# ramanPi_controlBoard.net
KiCad netlist of a schematic drawn in EAGLE
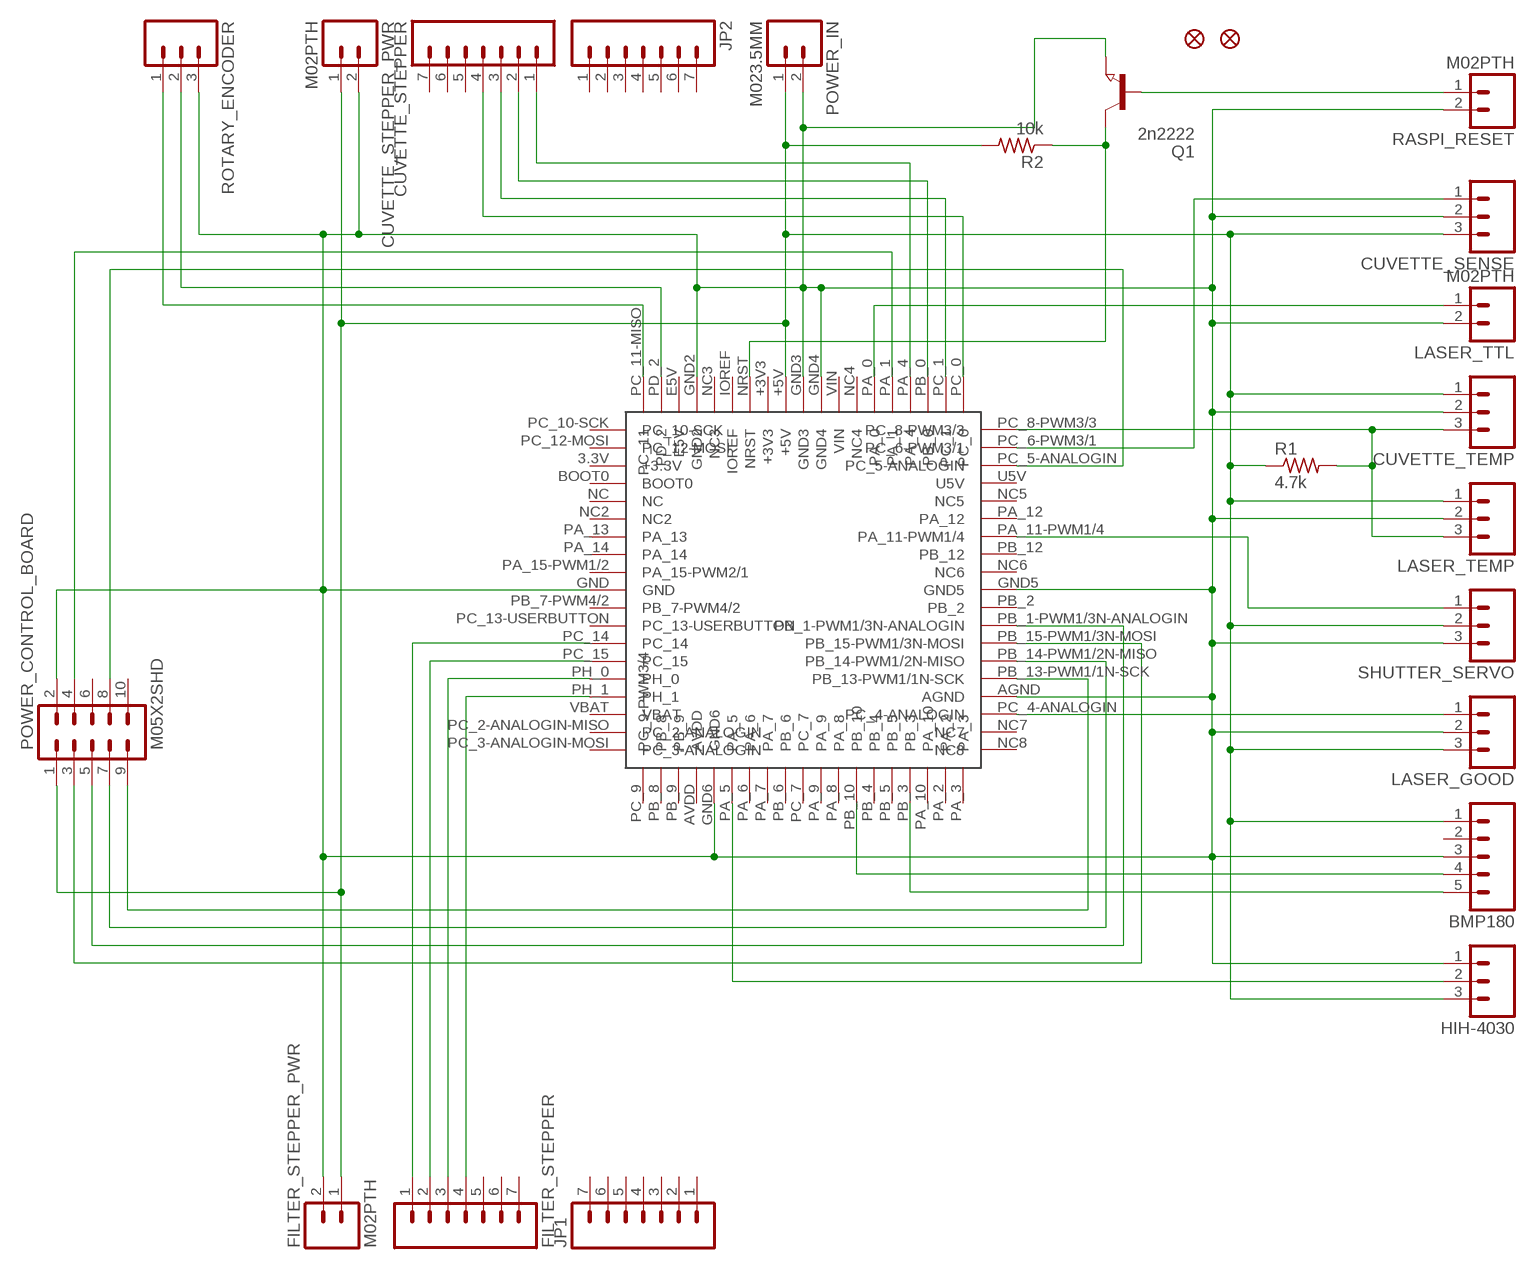
[diagram p0: schematic, sheet 1]

(export (version "E")
  (design (tool "Eeschema 10.0.6"))
  (components
    (comp (ref "BMP180")
      (value "M05PTH")
      (footprint "eagle-import:1X05")
      (libsource (lib "eagle-import") (part "M05PTH"))
    )
    (comp (ref "CUVETTE_SENSE")
      (value "M03PTH")
      (footprint "eagle-import:1X03")
      (libsource (lib "eagle-import") (part "M03PTH"))
    )
    (comp (ref "CUVETTE_STEPPER")
      (value "M07")
      (footprint "eagle-import:1X07")
      (libsource (lib "eagle-import") (part "M07"))
    )
    (comp (ref "CUVETTE_STEPPER_PWR")
      (value "M02PTH")
      (footprint "eagle-import:1X02")
      (libsource (lib "eagle-import") (part "M02PTH"))
    )
    (comp (ref "CUVETTE_TEMP")
      (value "M03PTH")
      (footprint "eagle-import:1X03")
      (libsource (lib "eagle-import") (part "M03PTH"))
    )
    (comp (ref "FID1")
      (value "FIDUCIAL1X2")
      (footprint "eagle-import:FIDUCIAL-1X2")
      (libsource (lib "eagle-import") (part "FIDUCIAL1X2"))
    )
    (comp (ref "FID2")
      (value "FIDUCIAL1X2")
      (footprint "eagle-import:FIDUCIAL-1X2")
      (libsource (lib "eagle-import") (part "FIDUCIAL1X2"))
    )
    (comp (ref "FILTER_STEPPER")
      (value "M07")
      (footprint "eagle-import:1X07")
      (libsource (lib "eagle-import") (part "M07"))
    )
    (comp (ref "FILTER_STEPPER_PWR")
      (value "M02PTH")
      (footprint "eagle-import:1X02")
      (libsource (lib "eagle-import") (part "M02PTH"))
    )
    (comp (ref "HIH-4030")
      (value "M03PTH")
      (footprint "eagle-import:1X03")
      (libsource (lib "eagle-import") (part "M03PTH"))
    )
    (comp (ref "JP1")
      (value "M07")
      (footprint "eagle-import:1X07")
      (libsource (lib "eagle-import") (part "M07"))
    )
    (comp (ref "JP2")
      (value "M07")
      (footprint "eagle-import:1X07")
      (libsource (lib "eagle-import") (part "M07"))
    )
    (comp (ref "LASER_GOOD")
      (value "M03PTH")
      (footprint "eagle-import:1X03")
      (libsource (lib "eagle-import") (part "M03PTH"))
    )
    (comp (ref "LASER_TEMP")
      (value "M03PTH")
      (footprint "eagle-import:1X03")
      (libsource (lib "eagle-import") (part "M03PTH"))
    )
    (comp (ref "LASER_TTL")
      (value "M02PTH")
      (footprint "eagle-import:1X02")
      (libsource (lib "eagle-import") (part "M02PTH"))
    )
    (comp (ref "POWER_CONTROL_BOARD")
      (value "M05X2SHD")
      (footprint "eagle-import:2X5-SHROUDED")
      (libsource (lib "eagle-import") (part "M05X2SHD"))
    )
    (comp (ref "POWER_IN")
      (value "M023.5MM")
      (footprint "eagle-import:SCREWTERMINAL-3.5MM-2")
      (libsource (lib "eagle-import") (part "M023.5MM"))
    )
    (comp (ref "Q1")
      (value "2n2222")
      (footprint "eagle-import:SOT23")
      (libsource (lib "eagle-import") (part "NPN-TRANSISTOR_SOT23"))
    )
    (comp (ref "R1")
      (value "4.7k")
      (footprint "eagle-import:M1206")
      (libsource (lib "eagle-import") (part "R-US_M1206"))
    )
    (comp (ref "R2")
      (value "10k")
      (footprint "eagle-import:M1206")
      (libsource (lib "eagle-import") (part "R-US_M1206"))
    )
    (comp (ref "RASPI_RESET")
      (value "M02PTH")
      (footprint "eagle-import:1X02")
      (libsource (lib "eagle-import") (part "M02PTH"))
    )
    (comp (ref "ROTARY_ENCODER")
      (value "M03PTH")
      (footprint "eagle-import:1X03")
      (libsource (lib "eagle-import") (part "M03PTH"))
    )
    (comp (ref "SHUTTER_SERVO")
      (value "M03PTH")
      (footprint "eagle-import:1X03")
      (libsource (lib "eagle-import") (part "M03PTH"))
    )
    (comp (ref "U$1")
      (value "STNUCLEOF401RE")
      (footprint "eagle-import:F401-RE")
      (libsource (lib "eagle-import") (part "STNUCLEOF401RE"))
    )
  )
  (nets
    (net (code "1") (name "/+3.3V") (class "Default")
      (node (ref "U$1") (pin "3.3V") (pinfunction "+3.3V_3.3V") (pintype "power_in"))
    )
    (net (code "2") (name "/+3V3") (class "Default")
      (node (ref "U$1") (pin "+3V3") (pinfunction "+3V3_+3V3") (pintype "power_in"))
    )
    (net (code "3") (name "/AVDD") (class "Default")
      (node (ref "U$1") (pin "AVDD") (pinfunction "AVDD_AVDD") (pintype "power_in"))
    )
    (net (code "4") (name "/E5V") (class "Default")
      (node (ref "U$1") (pin "E5V") (pinfunction "E5V_E5V") (pintype "power_in"))
    )
    (net (code "5") (name "/U5V") (class "Default")
      (node (ref "U$1") (pin "U5V") (pinfunction "U5V_U5V") (pintype "power_in"))
    )
    (net (code "6") (name "/VBAT") (class "Default")
      (node (ref "U$1") (pin "VBAT") (pinfunction "VBAT_VBAT") (pintype "power_in"))
    )
    (net (code "7") (name "/VIN") (class "Default")
      (node (ref "U$1") (pin "VIN") (pinfunction "VIN_VIN") (pintype "power_in"))
    )
    (net (code "8") (name "Net-(BMP180-Pad1)") (class "Default")
      (node (ref "BMP180") (pin "1") (pinfunction "1_1") (pintype "passive"))
      (node (ref "CUVETTE_SENSE") (pin "3") (pinfunction "3_3") (pintype "passive"))
      (node (ref "CUVETTE_STEPPER_PWR") (pin "1") (pinfunction "1_1") (pintype "passive"))
      (node (ref "CUVETTE_TEMP") (pin "1") (pinfunction "1_1") (pintype "passive"))
      (node (ref "FILTER_STEPPER_PWR") (pin "1") (pinfunction "1_1") (pintype "passive"))
      (node (ref "HIH-4030") (pin "3") (pinfunction "3_3") (pintype "passive"))
      (node (ref "LASER_GOOD") (pin "3") (pinfunction "3_3") (pintype "passive"))
      (node (ref "LASER_TEMP") (pin "1") (pinfunction "1_1") (pintype "passive"))
      (node (ref "POWER_CONTROL_BOARD") (pin "1") (pinfunction "1_1") (pintype "passive"))
      (node (ref "POWER_IN") (pin "1") (pinfunction "1_1") (pintype "passive"))
      (node (ref "R1") (pin "1") (pinfunction "1_1") (pintype "passive"))
      (node (ref "R2") (pin "2") (pinfunction "2_2") (pintype "passive"))
      (node (ref "SHUTTER_SERVO") (pin "2") (pinfunction "2_2") (pintype "passive"))
      (node (ref "U$1") (pin "+5V") (pinfunction "+5V_+5V") (pintype "power_in"))
    )
    (net (code "9") (name "Net-(BMP180-Pad4)") (class "Default")
      (node (ref "BMP180") (pin "4") (pinfunction "4_4") (pintype "passive"))
      (node (ref "U$1") (pin "PB_10") (pinfunction "PB_10_PB_10") (pintype "bidirectional"))
    )
    (net (code "10") (name "Net-(BMP180-Pad5)") (class "Default")
      (node (ref "BMP180") (pin "5") (pinfunction "5_5") (pintype "passive"))
      (node (ref "U$1") (pin "PB_3") (pinfunction "PB_3_PB_3") (pintype "bidirectional"))
    )
    (net (code "11") (name "Net-(CUVETTE_SENSE-Pad1)") (class "Default")
      (node (ref "CUVETTE_SENSE") (pin "1") (pinfunction "1_1") (pintype "passive"))
      (node (ref "U$1") (pin "PC_6-PWM3/1") (pinfunction "PC_6-PWM3/1_PC_6-PWM3/1") (pintype "bidirectional"))
    )
    (net (code "12") (name "Net-(CUVETTE_STEPPER-Pad1)") (class "Default")
      (node (ref "CUVETTE_STEPPER") (pin "1") (pinfunction "1_1") (pintype "passive"))
      (node (ref "U$1") (pin "PA_4") (pinfunction "PA_4_PA_4") (pintype "bidirectional"))
    )
    (net (code "13") (name "Net-(CUVETTE_STEPPER-Pad2)") (class "Default")
      (node (ref "CUVETTE_STEPPER") (pin "2") (pinfunction "2_2") (pintype "passive"))
      (node (ref "U$1") (pin "PB_0") (pinfunction "PB_0_PB_0") (pintype "bidirectional"))
    )
    (net (code "14") (name "Net-(CUVETTE_STEPPER-Pad3)") (class "Default")
      (node (ref "CUVETTE_STEPPER") (pin "3") (pinfunction "3_3") (pintype "passive"))
      (node (ref "U$1") (pin "PC_1") (pinfunction "PC_1_PC_1") (pintype "bidirectional"))
    )
    (net (code "15") (name "Net-(CUVETTE_STEPPER-Pad4)") (class "Default")
      (node (ref "CUVETTE_STEPPER") (pin "4") (pinfunction "4_4") (pintype "passive"))
      (node (ref "U$1") (pin "PC_0") (pinfunction "PC_0_PC_0") (pintype "bidirectional"))
    )
    (net (code "16") (name "Net-(CUVETTE_TEMP-Pad3)") (class "Default")
      (node (ref "CUVETTE_TEMP") (pin "3") (pinfunction "3_3") (pintype "passive"))
      (node (ref "LASER_TEMP") (pin "3") (pinfunction "3_3") (pintype "passive"))
      (node (ref "R1") (pin "2") (pinfunction "2_2") (pintype "passive"))
      (node (ref "U$1") (pin "PC_8-PWM3/3") (pinfunction "PC_8-PWM3/3_PC_8-PWM3/3") (pintype "bidirectional"))
    )
    (net (code "17") (name "Net-(FILTER_STEPPER-Pad1)") (class "Default")
      (node (ref "FILTER_STEPPER") (pin "1") (pinfunction "1_1") (pintype "passive"))
      (node (ref "U$1") (pin "PC_14") (pinfunction "PC_14_PC_14") (pintype "bidirectional"))
    )
    (net (code "18") (name "Net-(FILTER_STEPPER-Pad2)") (class "Default")
      (node (ref "FILTER_STEPPER") (pin "2") (pinfunction "2_2") (pintype "passive"))
      (node (ref "U$1") (pin "PC_15") (pinfunction "PC_15_PC_15") (pintype "bidirectional"))
    )
    (net (code "19") (name "Net-(FILTER_STEPPER-Pad3)") (class "Default")
      (node (ref "FILTER_STEPPER") (pin "3") (pinfunction "3_3") (pintype "passive"))
      (node (ref "U$1") (pin "PH_0") (pinfunction "PH_0_PH_0") (pintype "bidirectional"))
    )
    (net (code "20") (name "Net-(FILTER_STEPPER-Pad4)") (class "Default")
      (node (ref "FILTER_STEPPER") (pin "4") (pinfunction "4_4") (pintype "passive"))
      (node (ref "U$1") (pin "PH_1") (pinfunction "PH_1_PH_1") (pintype "bidirectional"))
    )
    (net (code "21") (name "Net-(HIH-4030-Pad2)") (class "Default")
      (node (ref "HIH-4030") (pin "2") (pinfunction "2_2") (pintype "passive"))
      (node (ref "U$1") (pin "PA_5") (pinfunction "PA_5_PA_5") (pintype "bidirectional"))
    )
    (net (code "22") (name "Net-(LASER_GOOD-Pad1)") (class "Default")
      (node (ref "LASER_GOOD") (pin "1") (pinfunction "1_1") (pintype "passive"))
      (node (ref "U$1") (pin "PC_4-ANALOGIN") (pinfunction "PC_4-ANALOGIN_PC_4-ANALOGIN") (pintype "bidirectional"))
    )
    (net (code "23") (name "Net-(LASER_TTL-Pad1)") (class "Default")
      (node (ref "LASER_TTL") (pin "1") (pinfunction "1_1") (pintype "passive"))
      (node (ref "U$1") (pin "PA_0") (pinfunction "PA_0_PA_0") (pintype "bidirectional"))
    )
    (net (code "24") (name "Net-(POWER_CONTROL_BOARD-Pad3)") (class "Default")
      (node (ref "POWER_CONTROL_BOARD") (pin "3") (pinfunction "3_3") (pintype "passive"))
      (node (ref "U$1") (pin "PB_15-PWM1/3N-MOSI") (pinfunction "PB_15-PWM1/3N-MOSI_PB_15-PWM1/3N-MOSI") (pintype "bidirectional"))
    )
    (net (code "25") (name "Net-(POWER_CONTROL_BOARD-Pad4)") (class "Default")
      (node (ref "POWER_CONTROL_BOARD") (pin "4") (pinfunction "4_4") (pintype "passive"))
      (node (ref "U$1") (pin "PA_1") (pinfunction "PA_1_PA_1") (pintype "bidirectional"))
    )
    (net (code "26") (name "Net-(POWER_CONTROL_BOARD-Pad5)") (class "Default")
      (node (ref "POWER_CONTROL_BOARD") (pin "5") (pinfunction "5_5") (pintype "passive"))
      (node (ref "U$1") (pin "PB_1-PWM1/3N-ANALOGIN") (pinfunction "PB_1-PWM1/3N-ANALOGIN_PB_1-PWM1/3N-ANALOGIN") (pintype "bidirectional"))
    )
    (net (code "27") (name "Net-(POWER_CONTROL_BOARD-Pad7)") (class "Default")
      (node (ref "POWER_CONTROL_BOARD") (pin "7") (pinfunction "7_7") (pintype "passive"))
      (node (ref "U$1") (pin "PB_14-PWM1/2N-MISO") (pinfunction "PB_14-PWM1/2N-MISO_PB_14-PWM1/2N-MISO") (pintype "bidirectional"))
    )
    (net (code "28") (name "Net-(POWER_CONTROL_BOARD-Pad8)") (class "Default")
      (node (ref "POWER_CONTROL_BOARD") (pin "8") (pinfunction "8_8") (pintype "passive"))
      (node (ref "U$1") (pin "PC_5-ANALOGIN") (pinfunction "PC_5-ANALOGIN_PC_5-ANALOGIN") (pintype "bidirectional"))
    )
    (net (code "29") (name "Net-(POWER_CONTROL_BOARD-Pad9)") (class "Default")
      (node (ref "POWER_CONTROL_BOARD") (pin "9") (pinfunction "9_9") (pintype "passive"))
      (node (ref "U$1") (pin "PB_13-PWM1/1N-SCK") (pinfunction "PB_13-PWM1/1N-SCK_PB_13-PWM1/1N-SCK") (pintype "bidirectional"))
    )
    (net (code "30") (name "Net-(Q1-B)") (class "Default")
      (node (ref "Q1") (pin "1") (pinfunction "B_1") (pintype "passive"))
      (node (ref "RASPI_RESET") (pin "1") (pinfunction "1_1") (pintype "passive"))
    )
    (net (code "31") (name "Net-(Q1-C)") (class "Default")
      (node (ref "Q1") (pin "3") (pinfunction "C_3") (pintype "passive"))
      (node (ref "R2") (pin "1") (pinfunction "1_1") (pintype "passive"))
      (node (ref "U$1") (pin "NRST") (pinfunction "NRST_NRST") (pintype "bidirectional"))
    )
    (net (code "32") (name "Net-(Q1-E)") (class "Default")
      (node (ref "BMP180") (pin "3") (pinfunction "3_3") (pintype "passive"))
      (node (ref "CUVETTE_SENSE") (pin "2") (pinfunction "2_2") (pintype "passive"))
      (node (ref "CUVETTE_STEPPER_PWR") (pin "2") (pinfunction "2_2") (pintype "passive"))
      (node (ref "CUVETTE_TEMP") (pin "2") (pinfunction "2_2") (pintype "passive"))
      (node (ref "FILTER_STEPPER_PWR") (pin "2") (pinfunction "2_2") (pintype "passive"))
      (node (ref "HIH-4030") (pin "1") (pinfunction "1_1") (pintype "passive"))
      (node (ref "LASER_GOOD") (pin "2") (pinfunction "2_2") (pintype "passive"))
      (node (ref "LASER_TEMP") (pin "2") (pinfunction "2_2") (pintype "passive"))
      (node (ref "LASER_TTL") (pin "2") (pinfunction "2_2") (pintype "passive"))
      (node (ref "POWER_CONTROL_BOARD") (pin "2") (pinfunction "2_2") (pintype "passive"))
      (node (ref "POWER_IN") (pin "2") (pinfunction "2_2") (pintype "passive"))
      (node (ref "Q1") (pin "2") (pinfunction "E_2") (pintype "passive"))
      (node (ref "RASPI_RESET") (pin "2") (pinfunction "2_2") (pintype "passive"))
      (node (ref "ROTARY_ENCODER") (pin "3") (pinfunction "3_3") (pintype "passive"))
      (node (ref "SHUTTER_SERVO") (pin "3") (pinfunction "3_3") (pintype "passive"))
      (node (ref "U$1") (pin "AGND") (pinfunction "AGND_AGND") (pintype "power_in"))
      (node (ref "U$1") (pin "GND") (pinfunction "GND_GND") (pintype "power_in"))
      (node (ref "U$1") (pin "GND2") (pinfunction "GND2_GND2") (pintype "power_in"))
      (node (ref "U$1") (pin "GND3") (pinfunction "GND3_GND3") (pintype "power_in"))
      (node (ref "U$1") (pin "GND4") (pinfunction "GND4_GND4") (pintype "power_in"))
      (node (ref "U$1") (pin "GND5") (pinfunction "GND5_GND5") (pintype "power_in"))
      (node (ref "U$1") (pin "GND6") (pinfunction "GND6_GND6") (pintype "power_in"))
    )
    (net (code "33") (name "Net-(ROTARY_ENCODER-Pad2)") (class "Default")
      (node (ref "ROTARY_ENCODER") (pin "2") (pinfunction "2_2") (pintype "passive"))
      (node (ref "U$1") (pin "PD_2") (pinfunction "PD_2_PD_2") (pintype "bidirectional"))
    )
    (net (code "34") (name "Net-(SHUTTER_SERVO-Pad1)") (class "Default")
      (node (ref "SHUTTER_SERVO") (pin "1") (pinfunction "1_1") (pintype "passive"))
      (node (ref "U$1") (pin "PA_11-PWM1/4") (pinfunction "PA_11-PWM1/4_PA_11-PWM1/4") (pintype "bidirectional"))
    )
    (net (code "35") (name "Net-(U$1-PC_11)") (class "Default")
      (node (ref "ROTARY_ENCODER") (pin "1") (pinfunction "1_1") (pintype "passive"))
      (node (ref "U$1") (pin "PC_11-MISO") (pinfunction "PC_11_PC_11-MISO") (pintype "bidirectional"))
    )
    (net (code "36") (name "unconnected-(BMP180-Pad2)") (class "Default")
      (node (ref "BMP180") (pin "2") (pinfunction "2_2") (pintype "passive"))
    )
    (net (code "37") (name "unconnected-(CUVETTE_STEPPER-Pad5)") (class "Default")
      (node (ref "CUVETTE_STEPPER") (pin "5") (pinfunction "5_5") (pintype "passive"))
    )
    (net (code "38") (name "unconnected-(CUVETTE_STEPPER-Pad6)") (class "Default")
      (node (ref "CUVETTE_STEPPER") (pin "6") (pinfunction "6_6") (pintype "passive"))
    )
    (net (code "39") (name "unconnected-(CUVETTE_STEPPER-Pad7)") (class "Default")
      (node (ref "CUVETTE_STEPPER") (pin "7") (pinfunction "7_7") (pintype "passive"))
    )
    (net (code "40") (name "unconnected-(FILTER_STEPPER-Pad5)") (class "Default")
      (node (ref "FILTER_STEPPER") (pin "5") (pinfunction "5_5") (pintype "passive"))
    )
    (net (code "41") (name "unconnected-(FILTER_STEPPER-Pad6)") (class "Default")
      (node (ref "FILTER_STEPPER") (pin "6") (pinfunction "6_6") (pintype "passive"))
    )
    (net (code "42") (name "unconnected-(FILTER_STEPPER-Pad7)") (class "Default")
      (node (ref "FILTER_STEPPER") (pin "7") (pinfunction "7_7") (pintype "passive"))
    )
    (net (code "43") (name "unconnected-(JP1-Pad1)") (class "Default")
      (node (ref "JP1") (pin "1") (pinfunction "1_1") (pintype "passive"))
    )
    (net (code "44") (name "unconnected-(JP1-Pad2)") (class "Default")
      (node (ref "JP1") (pin "2") (pinfunction "2_2") (pintype "passive"))
    )
    (net (code "45") (name "unconnected-(JP1-Pad3)") (class "Default")
      (node (ref "JP1") (pin "3") (pinfunction "3_3") (pintype "passive"))
    )
    (net (code "46") (name "unconnected-(JP1-Pad4)") (class "Default")
      (node (ref "JP1") (pin "4") (pinfunction "4_4") (pintype "passive"))
    )
    (net (code "47") (name "unconnected-(JP1-Pad5)") (class "Default")
      (node (ref "JP1") (pin "5") (pinfunction "5_5") (pintype "passive"))
    )
    (net (code "48") (name "unconnected-(JP1-Pad6)") (class "Default")
      (node (ref "JP1") (pin "6") (pinfunction "6_6") (pintype "passive"))
    )
    (net (code "49") (name "unconnected-(JP1-Pad7)") (class "Default")
      (node (ref "JP1") (pin "7") (pinfunction "7_7") (pintype "passive"))
    )
    (net (code "50") (name "unconnected-(JP2-Pad1)") (class "Default")
      (node (ref "JP2") (pin "1") (pinfunction "1_1") (pintype "passive"))
    )
    (net (code "51") (name "unconnected-(JP2-Pad2)") (class "Default")
      (node (ref "JP2") (pin "2") (pinfunction "2_2") (pintype "passive"))
    )
    (net (code "52") (name "unconnected-(JP2-Pad3)") (class "Default")
      (node (ref "JP2") (pin "3") (pinfunction "3_3") (pintype "passive"))
    )
    (net (code "53") (name "unconnected-(JP2-Pad4)") (class "Default")
      (node (ref "JP2") (pin "4") (pinfunction "4_4") (pintype "passive"))
    )
    (net (code "54") (name "unconnected-(JP2-Pad5)") (class "Default")
      (node (ref "JP2") (pin "5") (pinfunction "5_5") (pintype "passive"))
    )
    (net (code "55") (name "unconnected-(JP2-Pad6)") (class "Default")
      (node (ref "JP2") (pin "6") (pinfunction "6_6") (pintype "passive"))
    )
    (net (code "56") (name "unconnected-(JP2-Pad7)") (class "Default")
      (node (ref "JP2") (pin "7") (pinfunction "7_7") (pintype "passive"))
    )
    (net (code "57") (name "unconnected-(POWER_CONTROL_BOARD-Pad6)") (class "Default")
      (node (ref "POWER_CONTROL_BOARD") (pin "6") (pinfunction "6_6") (pintype "passive"))
    )
    (net (code "58") (name "unconnected-(POWER_CONTROL_BOARD-Pad10)") (class "Default")
      (node (ref "POWER_CONTROL_BOARD") (pin "10") (pinfunction "10_10") (pintype "passive"))
    )
    (net (code "59") (name "unconnected-(U$1-PA_15-PWM2{slash}1-PadPA_15-PWM1{slash}2)") (class "Default")
      (node (ref "U$1") (pin "PA_15-PWM1/2") (pinfunction "PA_15-PWM2/1_PA_15-PWM1/2") (pintype "bidirectional"))
    )
    (net (code "60") (name "unconnected-(U$1-PC_2-ANALOGIN-PadPC_2-ANALOGIN-MISO)") (class "Default")
      (node (ref "U$1") (pin "PC_2-ANALOGIN-MISO") (pinfunction "PC_2-ANALOGIN_PC_2-ANALOGIN-MISO") (pintype "bidirectional"))
    )
    (net (code "61") (name "unconnected-(U$1-PC_3-ANALOGIN-PadPC_3-ANALOGIN-MOSI)") (class "Default")
      (node (ref "U$1") (pin "PC_3-ANALOGIN-MOSI") (pinfunction "PC_3-ANALOGIN_PC_3-ANALOGIN-MOSI") (pintype "bidirectional"))
    )
    (net (code "62") (name "unconnected-(U$1-PC_9-PWM3{slash}4-PadPC_9)") (class "Default")
      (node (ref "U$1") (pin "PC_9") (pinfunction "PC_9-PWM3/4_PC_9") (pintype "bidirectional"))
    )
    (net (code "63") (name "unconnected-(U$1-PadBOOT0)") (class "Default")
      (node (ref "U$1") (pin "BOOT0") (pinfunction "BOOT0_BOOT0") (pintype "bidirectional"))
    )
    (net (code "64") (name "unconnected-(U$1-PadIOREF)") (class "Default")
      (node (ref "U$1") (pin "IOREF") (pinfunction "IOREF_IOREF") (pintype "bidirectional"))
    )
    (net (code "65") (name "unconnected-(U$1-PadNC)") (class "Default")
      (node (ref "U$1") (pin "NC") (pinfunction "NC_NC") (pintype "no_connect"))
    )
    (net (code "66") (name "unconnected-(U$1-PadNC2)") (class "Default")
      (node (ref "U$1") (pin "NC2") (pinfunction "NC2_NC2") (pintype "no_connect"))
    )
    (net (code "67") (name "unconnected-(U$1-PadNC3)") (class "Default")
      (node (ref "U$1") (pin "NC3") (pinfunction "NC3_NC3") (pintype "no_connect"))
    )
    (net (code "68") (name "unconnected-(U$1-PadNC4)") (class "Default")
      (node (ref "U$1") (pin "NC4") (pinfunction "NC4_NC4") (pintype "bidirectional"))
    )
    (net (code "69") (name "unconnected-(U$1-PadNC5)") (class "Default")
      (node (ref "U$1") (pin "NC5") (pinfunction "NC5_NC5") (pintype "no_connect"))
    )
    (net (code "70") (name "unconnected-(U$1-PadNC6)") (class "Default")
      (node (ref "U$1") (pin "NC6") (pinfunction "NC6_NC6") (pintype "no_connect"))
    )
    (net (code "71") (name "unconnected-(U$1-PadNC7)") (class "Default")
      (node (ref "U$1") (pin "NC7") (pinfunction "NC7_NC7") (pintype "bidirectional"))
    )
    (net (code "72") (name "unconnected-(U$1-PadNC8)") (class "Default")
      (node (ref "U$1") (pin "NC8") (pinfunction "NC8_NC8") (pintype "bidirectional"))
    )
    (net (code "73") (name "unconnected-(U$1-PadPA_2)") (class "Default")
      (node (ref "U$1") (pin "PA_2") (pinfunction "PA_2_PA_2") (pintype "bidirectional"))
    )
    (net (code "74") (name "unconnected-(U$1-PadPA_3)") (class "Default")
      (node (ref "U$1") (pin "PA_3") (pinfunction "PA_3_PA_3") (pintype "bidirectional"))
    )
    (net (code "75") (name "unconnected-(U$1-PadPA_6)") (class "Default")
      (node (ref "U$1") (pin "PA_6") (pinfunction "PA_6_PA_6") (pintype "bidirectional"))
    )
    (net (code "76") (name "unconnected-(U$1-PadPA_7)") (class "Default")
      (node (ref "U$1") (pin "PA_7") (pinfunction "PA_7_PA_7") (pintype "bidirectional"))
    )
    (net (code "77") (name "unconnected-(U$1-PadPA_8)") (class "Default")
      (node (ref "U$1") (pin "PA_8") (pinfunction "PA_8_PA_8") (pintype "bidirectional"))
    )
    (net (code "78") (name "unconnected-(U$1-PadPA_9)") (class "Default")
      (node (ref "U$1") (pin "PA_9") (pinfunction "PA_9_PA_9") (pintype "bidirectional"))
    )
    (net (code "79") (name "unconnected-(U$1-PadPA_10)") (class "Default")
      (node (ref "U$1") (pin "PA_10") (pinfunction "PA_10_PA_10") (pintype "bidirectional"))
    )
    (net (code "80") (name "unconnected-(U$1-PadPA_12)") (class "Default")
      (node (ref "U$1") (pin "PA_12") (pinfunction "PA_12_PA_12") (pintype "bidirectional"))
    )
    (net (code "81") (name "unconnected-(U$1-PadPA_13)") (class "Default")
      (node (ref "U$1") (pin "PA_13") (pinfunction "PA_13_PA_13") (pintype "bidirectional"))
    )
    (net (code "82") (name "unconnected-(U$1-PadPA_14)") (class "Default")
      (node (ref "U$1") (pin "PA_14") (pinfunction "PA_14_PA_14") (pintype "bidirectional"))
    )
    (net (code "83") (name "unconnected-(U$1-PadPB_2)") (class "Default")
      (node (ref "U$1") (pin "PB_2") (pinfunction "PB_2_PB_2") (pintype "bidirectional"))
    )
    (net (code "84") (name "unconnected-(U$1-PadPB_4)") (class "Default")
      (node (ref "U$1") (pin "PB_4") (pinfunction "PB_4_PB_4") (pintype "bidirectional"))
    )
    (net (code "85") (name "unconnected-(U$1-PadPB_5)") (class "Default")
      (node (ref "U$1") (pin "PB_5") (pinfunction "PB_5_PB_5") (pintype "bidirectional"))
    )
    (net (code "86") (name "unconnected-(U$1-PadPB_6)") (class "Default")
      (node (ref "U$1") (pin "PB_6") (pinfunction "PB_6_PB_6") (pintype "bidirectional"))
    )
    (net (code "87") (name "unconnected-(U$1-PadPB_7-PWM4{slash}2)") (class "Default")
      (node (ref "U$1") (pin "PB_7-PWM4/2") (pinfunction "PB_7-PWM4/2_PB_7-PWM4/2") (pintype "bidirectional"))
    )
    (net (code "88") (name "unconnected-(U$1-PadPB_8)") (class "Default")
      (node (ref "U$1") (pin "PB_8") (pinfunction "PB_8_PB_8") (pintype "bidirectional"))
    )
    (net (code "89") (name "unconnected-(U$1-PadPB_9)") (class "Default")
      (node (ref "U$1") (pin "PB_9") (pinfunction "PB_9_PB_9") (pintype "bidirectional"))
    )
    (net (code "90") (name "unconnected-(U$1-PadPB_12)") (class "Default")
      (node (ref "U$1") (pin "PB_12") (pinfunction "PB_12_PB_12") (pintype "bidirectional"))
    )
    (net (code "91") (name "unconnected-(U$1-PadPC_7)") (class "Default")
      (node (ref "U$1") (pin "PC_7") (pinfunction "PC_7_PC_7") (pintype "bidirectional"))
    )
    (net (code "92") (name "unconnected-(U$1-PadPC_10-SCK)") (class "Default")
      (node (ref "U$1") (pin "PC_10-SCK") (pinfunction "PC_10-SCK_PC_10-SCK") (pintype "bidirectional"))
    )
    (net (code "93") (name "unconnected-(U$1-PadPC_12-MOSI)") (class "Default")
      (node (ref "U$1") (pin "PC_12-MOSI") (pinfunction "PC_12-MOSI_PC_12-MOSI") (pintype "bidirectional"))
    )
    (net (code "94") (name "unconnected-(U$1-PadPC_13-USERBUTTON)") (class "Default")
      (node (ref "U$1") (pin "PC_13-USERBUTTON") (pinfunction "PC_13-USERBUTTON_PC_13-USERBUTTON") (pintype "bidirectional"))
    )
  )
)
